# altium_sample.net
KiCad netlist of a schematic drawn in Altium Designer
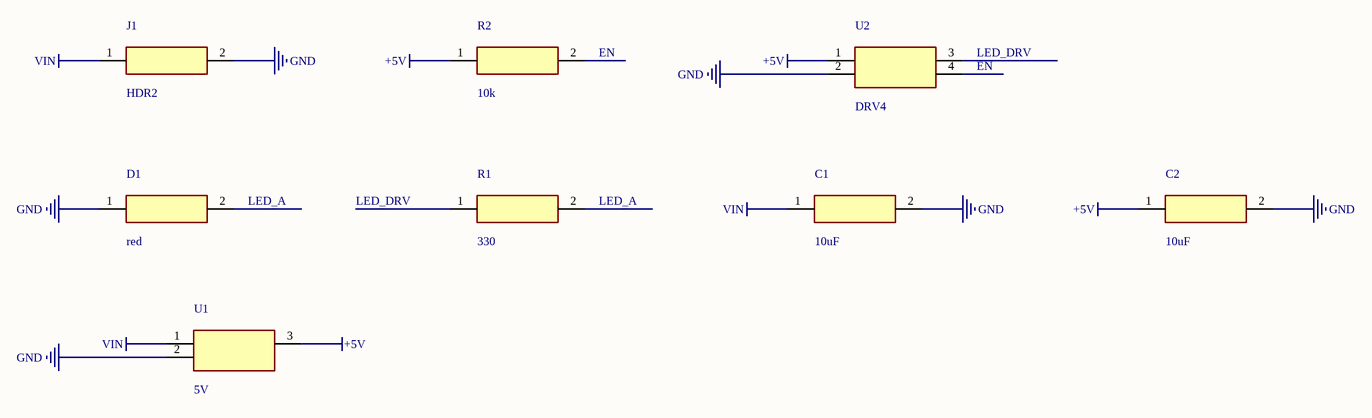
[diagram p0: altium_sample.SchDoc]

(export (version "E")
  (design (tool "Eeschema 10.0.6"))
  (components
    (comp (ref "C1")
      (value "10uF")
      (footprint "FenoliteSample:C0603")
      (libsource (lib "FenoliteSample") (part "CAP"))
    )
    (comp (ref "C2")
      (value "10uF")
      (footprint "FenoliteSample:C0603")
      (libsource (lib "FenoliteSample") (part "CAP"))
    )
    (comp (ref "D1")
      (value "red")
      (footprint "FenoliteSample:LED0603")
      (libsource (lib "FenoliteSample") (part "LED"))
    )
    (comp (ref "J1")
      (value "HDR2")
      (footprint "FenoliteSample:HDR1X2")
      (libsource (lib "FenoliteSample") (part "HDR2"))
    )
    (comp (ref "R1")
      (value "330")
      (footprint "FenoliteSample:R0603")
      (libsource (lib "FenoliteSample") (part "RES"))
    )
    (comp (ref "R2")
      (value "10k")
      (footprint "FenoliteSample:R0603")
      (libsource (lib "FenoliteSample") (part "RES"))
    )
    (comp (ref "U1")
      (value "5V")
      (footprint "FenoliteSample:SOT23")
      (libsource (lib "FenoliteSample") (part "LDO3"))
    )
    (comp (ref "U2")
      (value "DRV4")
      (footprint "FenoliteSample:SOT143")
      (libsource (lib "FenoliteSample") (part "DRV4"))
    )
  )
  (nets
    (net (code "1") (name "+5V") (class "Default")
      (node (ref "C2") (pin "1") (pinfunction "1_1") (pintype "passive"))
      (node (ref "R2") (pin "1") (pinfunction "1_1") (pintype "passive"))
      (node (ref "U1") (pin "3") (pinfunction "3_3") (pintype "passive"))
      (node (ref "U2") (pin "1") (pinfunction "1_1") (pintype "passive"))
    )
    (net (code "2") (name "/EN") (class "Default")
      (node (ref "R2") (pin "2") (pinfunction "2_2") (pintype "passive"))
      (node (ref "U2") (pin "4") (pinfunction "4_4") (pintype "passive"))
    )
    (net (code "3") (name "/LED_A") (class "Default")
      (node (ref "D1") (pin "2") (pinfunction "2_2") (pintype "passive"))
      (node (ref "R1") (pin "2") (pinfunction "2_2") (pintype "passive"))
    )
    (net (code "4") (name "/LED_DRV") (class "Default")
      (node (ref "R1") (pin "1") (pinfunction "1_1") (pintype "passive"))
      (node (ref "U2") (pin "3") (pinfunction "3_3") (pintype "passive"))
    )
    (net (code "5") (name "GND") (class "Default")
      (node (ref "C1") (pin "2") (pinfunction "2_2") (pintype "passive"))
      (node (ref "C2") (pin "2") (pinfunction "2_2") (pintype "passive"))
      (node (ref "D1") (pin "1") (pinfunction "1_1") (pintype "passive"))
      (node (ref "J1") (pin "2") (pinfunction "2_2") (pintype "passive"))
      (node (ref "U1") (pin "2") (pinfunction "2_2") (pintype "passive"))
      (node (ref "U2") (pin "2") (pinfunction "2_2") (pintype "passive"))
    )
    (net (code "6") (name "VIN") (class "Default")
      (node (ref "C1") (pin "1") (pinfunction "1_1") (pintype "passive"))
      (node (ref "J1") (pin "1") (pinfunction "1_1") (pintype "passive"))
      (node (ref "U1") (pin "1") (pinfunction "1_1") (pintype "passive"))
    )
  )
)
